# Power_Soldier.net
KiCad netlist of a schematic drawn in Altium Designer
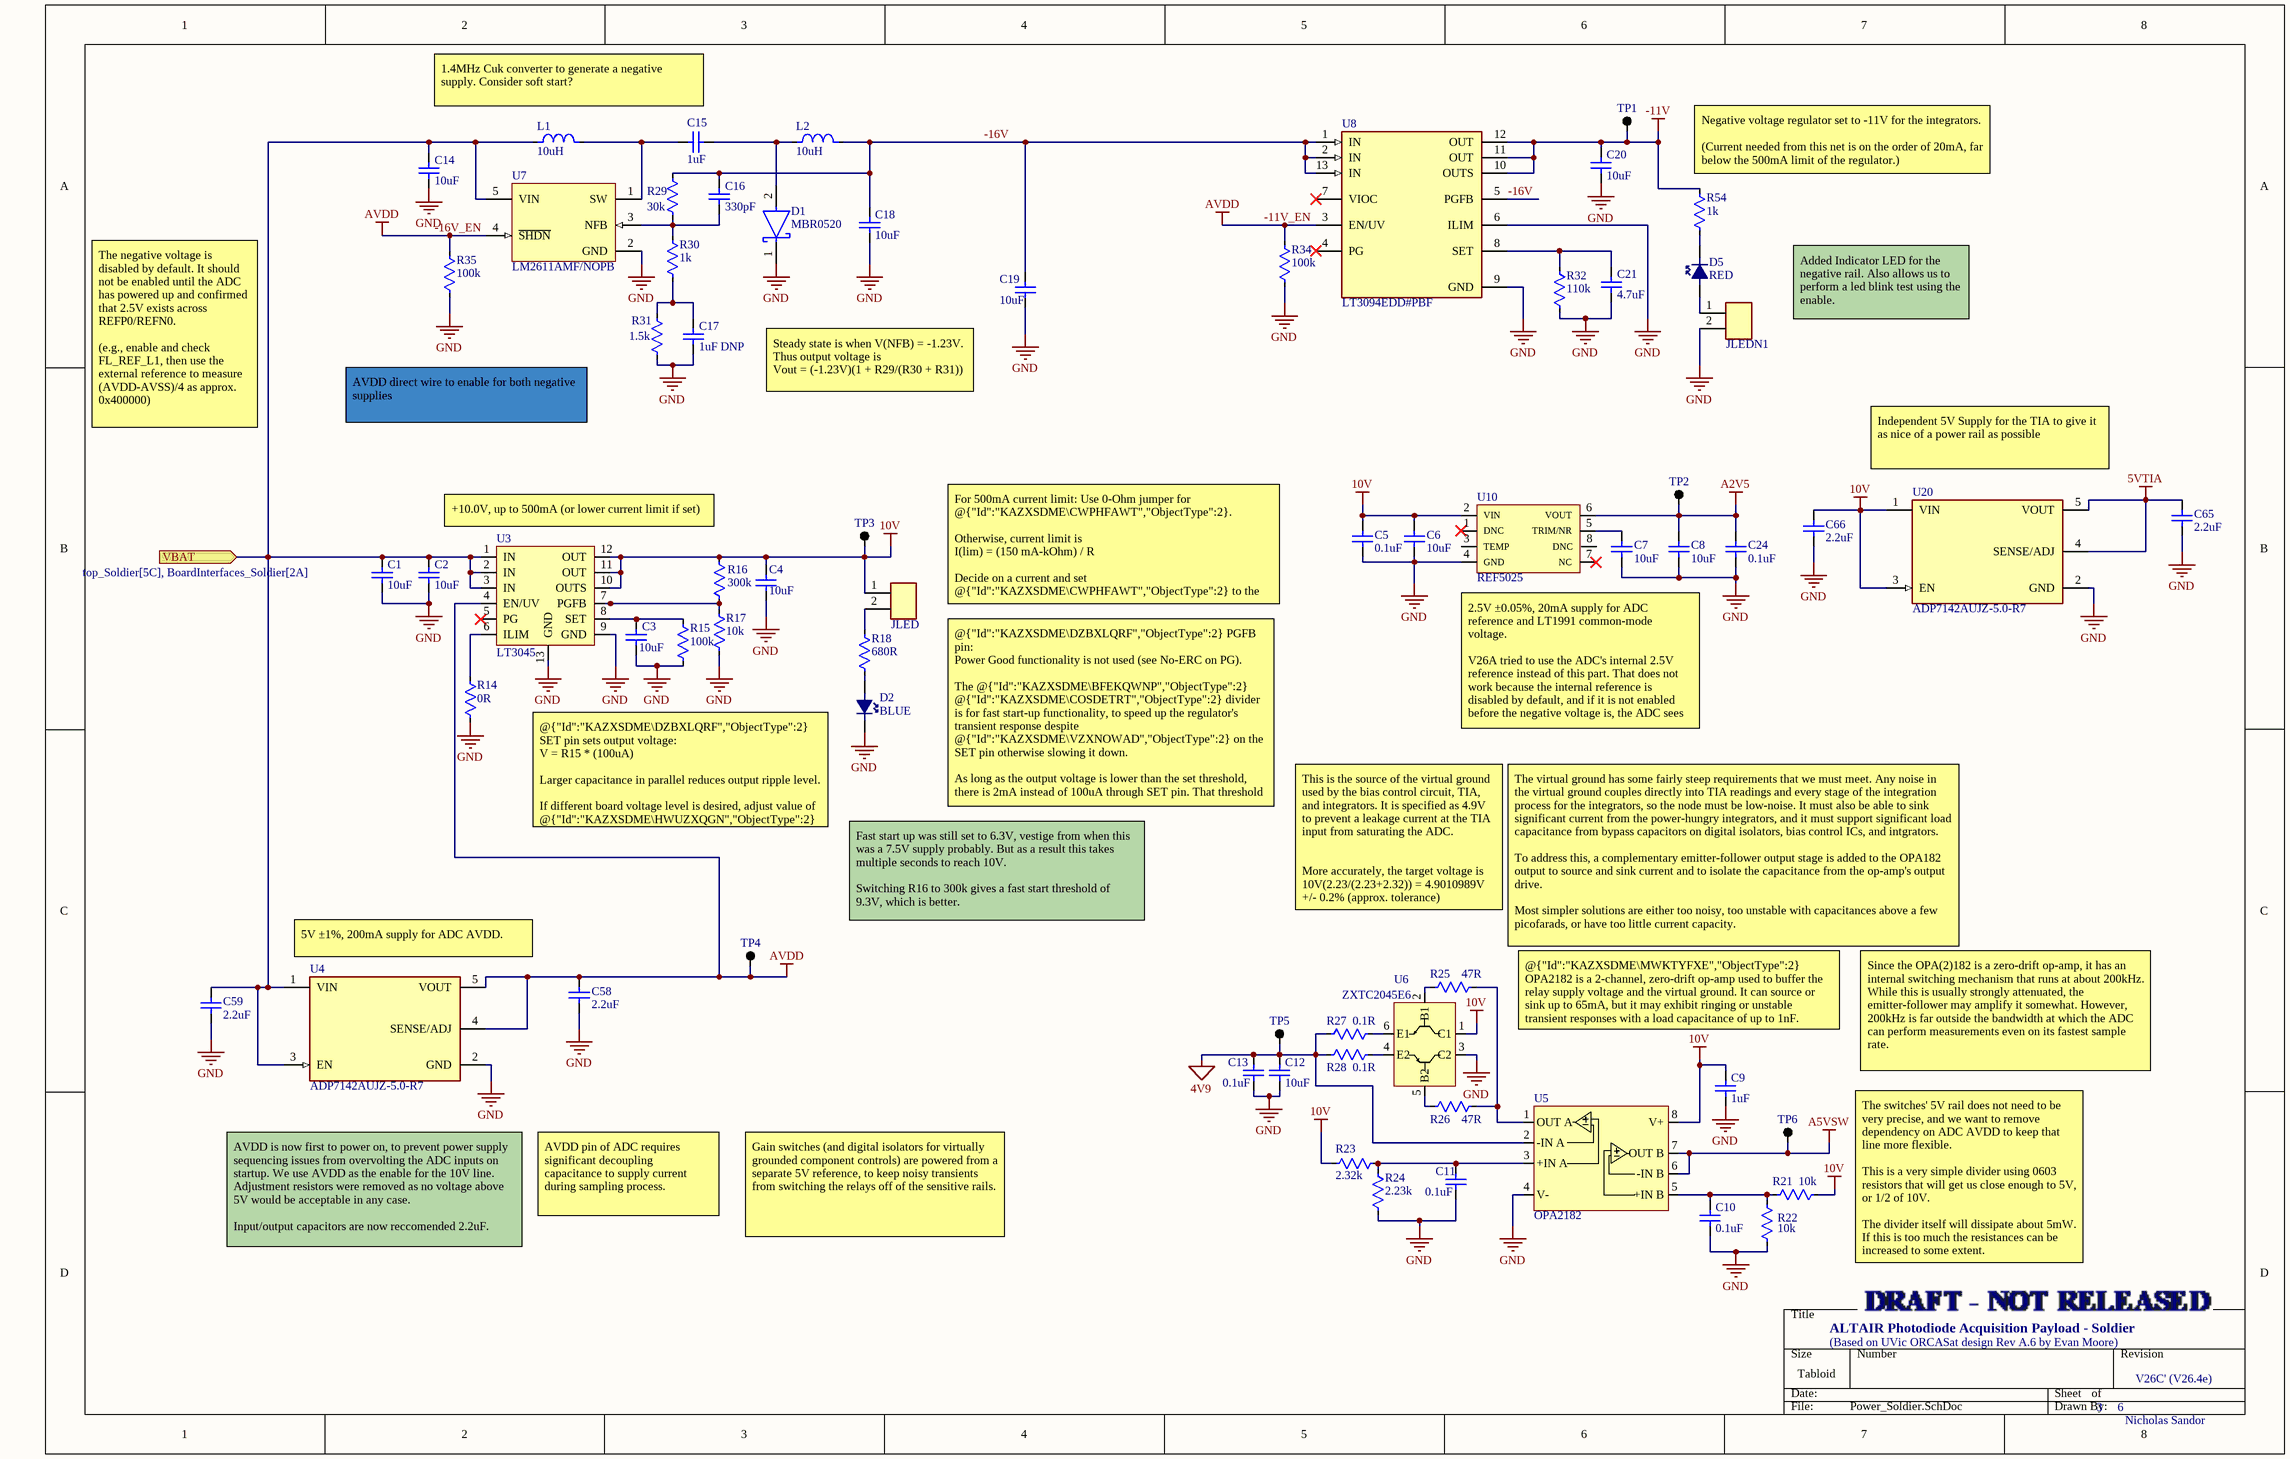
[diagram p0: Power_Soldier.SchDoc]

(export (version "E")
  (design (tool "Eeschema 10.0.6"))
  (components
    (comp (ref "C1")
      (value "10uF")
      (footprint "CAP 1206 IPC LOW DENSITY")
      (description "Murata GRT319R6YA106KE01D - Cap Ceramic 10uF 35V X5R 10% Pad SMD 1206 85C Automotive T/R")
      (fields (field (name "MF") "Murata") (field (name "MP") "GRT319R6YA106KE01D"))
      (libsource (lib "ALTAIR_PD_Capacitors") (part "CAP"))
    )
    (comp (ref "C2")
      (value "10uF")
      (footprint "CAP 1206 IPC LOW DENSITY")
      (description "Murata GRT319R6YA106KE01D - Cap Ceramic 10uF 35V X5R 10% Pad SMD 1206 85C Automotive T/R")
      (fields (field (name "MF") "Murata") (field (name "MP") "GRT319R6YA106KE01D"))
      (libsource (lib "ALTAIR_PD_Capacitors") (part "CAP"))
    )
    (comp (ref "C3")
      (value "10uF")
      (footprint "CAP 1206 IPC LOW DENSITY")
      (description "Murata GRT319R6YA106KE01D - Cap Ceramic 10uF 35V X5R 10% Pad SMD 1206 85C Automotive T/R")
      (fields (field (name "MF") "Murata") (field (name "MP") "GRT319R6YA106KE01D"))
      (libsource (lib "ALTAIR_PD_Capacitors") (part "CAP"))
    )
    (comp (ref "C4")
      (value "10uF")
      (footprint "CAP 1206 IPC LOW DENSITY")
      (description "Murata GRT319R6YA106KE01D - Cap Ceramic 10uF 35V X5R 10% Pad SMD 1206 85C Automotive T/R")
      (fields (field (name "MF") "Murata") (field (name "MP") "GRT319R6YA106KE01D"))
      (libsource (lib "ALTAIR_PD_Capacitors") (part "CAP"))
    )
    (comp (ref "C5")
      (value "0.1uF")
      (footprint "CAP 0603 IPC MID DENSITY")
      (description "Kemet C0603C104K5RACAUTO - Cap Ceramic 0.1uF 50V X7R 10% 0603 125C Paper T/R")
      (fields (field (name "MF") "Kemet") (field (name "MP") "C0603C104K5RACAUTO"))
      (libsource (lib "ALTAIR_PD_Capacitors") (part "CAP"))
    )
    (comp (ref "C6")
      (value "10uF")
      (footprint "CAP 0805 IPC MID DENSITY")
      (description "Murata GRM21BR61E106KA73L - Cap Ceramic 10uF 10% 25V X5R 0805")
      (fields (field (name "MF") "Murata") (field (name "MP") "GRM21BR61E106KA73L"))
      (libsource (lib "ALTAIR_PD_Capacitors") (part "CAP"))
    )
    (comp (ref "C7")
      (value "10uF")
      (footprint "CAP 0805 IPC MID DENSITY")
      (description "Murata GRM21BR61E106KA73L - Cap Ceramic 10uF 10% 25V X5R 0805")
      (fields (field (name "MF") "Murata") (field (name "MP") "GRM21BR61E106KA73L"))
      (libsource (lib "ALTAIR_PD_Capacitors") (part "CAP"))
    )
    (comp (ref "C8")
      (value "10uF")
      (footprint "CAP 0805 IPC MID DENSITY")
      (description "Murata GRM21BR61E106KA73L - Cap Ceramic 10uF 10% 25V X5R 0805")
      (fields (field (name "MF") "Murata") (field (name "MP") "GRM21BR61E106KA73L"))
      (libsource (lib "ALTAIR_PD_Capacitors") (part "CAP"))
    )
    (comp (ref "C9")
      (value "1uF")
      (footprint "CAP 0603 IPC MID DENSITY")
      (description "Murata GRT188R61H105KE13D - Cap MLCC AEC-Q200 X5R 1uF 50V 0603")
      (fields (field (name "MF") "Murata") (field (name "MP") "GRT188R61H105KE13D"))
      (libsource (lib "ALTAIR_PD_Capacitors") (part "CAP"))
    )
    (comp (ref "C10")
      (value "0.1uF")
      (footprint "CAP 0603 IPC MID DENSITY")
      (description "Kemet C0603C104K5RACAUTO - Cap Ceramic 0.1uF 50V X7R 10% 0603 125C Paper T/R")
      (fields (field (name "MF") "Kemet") (field (name "MP") "C0603C104K5RACAUTO"))
      (libsource (lib "ALTAIR_PD_Capacitors") (part "CAP"))
    )
    (comp (ref "C11")
      (value "0.1uF")
      (footprint "CAP 0603 IPC MID DENSITY")
      (description "Kemet C0603C104K5RACAUTO - Cap Ceramic 0.1uF 50V X7R 10% 0603 125C Paper T/R")
      (fields (field (name "MF") "Kemet") (field (name "MP") "C0603C104K5RACAUTO"))
      (libsource (lib "ALTAIR_PD_Capacitors") (part "CAP"))
    )
    (comp (ref "C12")
      (value "10uF")
      (footprint "CAP 1206 IPC LOW DENSITY")
      (description "Murata GRT319R6YA106KE01D - Cap Ceramic 10uF 35V X5R 10% Pad SMD 1206 85C Automotive T/R")
      (fields (field (name "MF") "Murata") (field (name "MP") "GRT319R6YA106KE01D"))
      (libsource (lib "ALTAIR_PD_Capacitors") (part "CAP"))
    )
    (comp (ref "C13")
      (value "0.1uF")
      (footprint "CAP 0603 IPC MID DENSITY")
      (description "Kemet C0603C104K5RACAUTO - Cap Ceramic 0.1uF 50V X7R 10% 0603 125C Paper T/R")
      (fields (field (name "MF") "Kemet") (field (name "MP") "C0603C104K5RACAUTO"))
      (libsource (lib "ALTAIR_PD_Capacitors") (part "CAP"))
    )
    (comp (ref "C14")
      (value "10uF")
      (footprint "CAP 0805 IPC MID DENSITY")
      (description "Murata GRM21BR61E106KA73L - Cap Ceramic 10uF 10% 25V X5R 0805")
      (fields (field (name "MF") "Murata") (field (name "MP") "GRM21BR61E106KA73L"))
      (libsource (lib "ALTAIR_PD_Capacitors") (part "CAP"))
    )
    (comp (ref "C15")
      (value "1uF")
      (footprint "CAP 0603 IPC MID DENSITY")
      (description "Murata GRT188R61H105KE13D - Cap MLCC AEC-Q200 X5R 1uF 50V 0603")
      (fields (field (name "MF") "Murata") (field (name "MP") "GRT188R61H105KE13D"))
      (libsource (lib "ALTAIR_PD_Capacitors") (part "CAP"))
    )
    (comp (ref "C16")
      (value "330pF")
      (footprint "CAP 1206 NON-IPC KEMET NP0")
      (description "Kemet C1206C331J5GACTU - Cap Ceramic 330pF 50V 5% NP0 1206")
      (fields (field (name "MF") "Kemet") (field (name "MP") "C1206C331J5GACTU"))
      (libsource (lib "ALTAIR_PD_Capacitors") (part "CAP"))
    )
    (comp (ref "C17")
      (value "1uF DNP")
      (footprint "CAP 0603 IPC MID DENSITY")
      (description "Murata GRT188R61H105KE13D - Cap MLCC AEC-Q200 X5R 1uF 50V 0603")
      (fields (field (name "MF") "Murata") (field (name "MP") "GRT188R61H105KE13D"))
      (libsource (lib "ALTAIR_PD_Capacitors") (part "CAP"))
    )
    (comp (ref "C18")
      (value "10uF")
      (footprint "CAP 0805 IPC MID DENSITY")
      (description "Murata GRM21BR61E106KA73L - Cap Ceramic 10uF 10% 25V X5R 0805")
      (fields (field (name "MF") "Murata") (field (name "MP") "GRM21BR61E106KA73L"))
      (libsource (lib "ALTAIR_PD_Capacitors") (part "CAP"))
    )
    (comp (ref "C19")
      (value "10uF")
      (footprint "CAP 0805 IPC MID DENSITY")
      (description "Murata GRM21BR61E106KA73L - Cap Ceramic 10uF 10% 25V X5R 0805")
      (fields (field (name "MF") "Murata") (field (name "MP") "GRM21BR61E106KA73L"))
      (libsource (lib "ALTAIR_PD_Capacitors") (part "CAP"))
    )
    (comp (ref "C20")
      (value "10uF")
      (footprint "CAP 0805 IPC MID DENSITY")
      (description "Murata GRM21BR61E106KA73L - Cap Ceramic 10uF 10% 25V X5R 0805")
      (fields (field (name "MF") "Murata") (field (name "MP") "GRM21BR61E106KA73L"))
      (libsource (lib "ALTAIR_PD_Capacitors") (part "CAP"))
    )
    (comp (ref "C21")
      (value "4.7uF")
      (footprint "CAP 0805 NON-IPC KEMET X5R")
      (description "Kemet C0805C475K8PACTU - Cap Ceramic 4.7uF 10V X5R 0805")
      (fields (field (name "MF") "Kemet") (field (name "MP") "C0805C475K8PACTU"))
      (libsource (lib "ALTAIR_PD_Capacitors") (part "CAP"))
    )
    (comp (ref "C24")
      (value "0.1uF")
      (footprint "CAP 0603 IPC MID DENSITY")
      (description "Kemet C0603C104K5RACAUTO - Cap Ceramic 0.1uF 50V X7R 10% 0603 125C Paper T/R")
      (fields (field (name "MF") "Kemet") (field (name "MP") "C0603C104K5RACAUTO"))
      (libsource (lib "ALTAIR_PD_Capacitors") (part "CAP"))
    )
    (comp (ref "C58")
      (value "2.2uF")
      (footprint "CAP 1206 UNKNOWN")
      (description "CL31B225KBHNNNE CAP CER 2.2UF 50V X7R 1206")
      (fields (field (name "MF") "Samsung Electro-Mechanics") (field (name "MP") "CL31B225KBHNNNE"))
      (libsource (lib "ALTAIR_PD_Capacitors") (part "CAP"))
    )
    (comp (ref "C59")
      (value "2.2uF")
      (footprint "CAP 1206 UNKNOWN")
      (description "CL31B225KBHNNNE CAP CER 2.2UF 50V X7R 1206")
      (fields (field (name "MF") "Samsung Electro-Mechanics") (field (name "MP") "CL31B225KBHNNNE"))
      (libsource (lib "ALTAIR_PD_Capacitors") (part "CAP"))
    )
    (comp (ref "C65")
      (value "2.2uF")
      (footprint "CAP 1206 UNKNOWN")
      (description "CL31B225KBHNNNE CAP CER 2.2UF 50V X7R 1206")
      (fields (field (name "MF") "Samsung Electro-Mechanics") (field (name "MP") "CL31B225KBHNNNE"))
      (libsource (lib "ALTAIR_PD_Capacitors") (part "CAP"))
    )
    (comp (ref "C66")
      (value "2.2uF")
      (footprint "CAP 1206 UNKNOWN")
      (description "CL31B225KBHNNNE CAP CER 2.2UF 50V X7R 1206")
      (fields (field (name "MF") "Samsung Electro-Mechanics") (field (name "MP") "CL31B225KBHNNNE"))
      (libsource (lib "ALTAIR_PD_Capacitors") (part "CAP"))
    )
    (comp (ref "D1")
      (value "MBR0520")
      (footprint "SOD-123 ONSEMI SMALL PADS")
      (description "DIODE SCHOTTKY 20V 500MA SOD123")
      (fields (field (name "MF") "onsemi") (field (name "MP") "MBR0520LT1G"))
      (libsource (lib "ALTAIR_PD_Diodes") (part "Schottky"))
    )
    (comp (ref "D2")
      (value "BLUE")
      (footprint "LED 0603 MID DENSITY")
      (description "LED BLUE CLEAR 0603 SMD")
      (fields (field (name "MF") "Wurth Electronics") (field (name "MP") "150060BS75000"))
      (libsource (lib "ALTAIR_PD_Diodes") (part "LED-blue"))
    )
    (comp (ref "D5")
      (value "RED")
      (footprint "LED 0603 MID DENSITY")
      (description "LED RED CLEAR 0603 SMD")
      (fields (field (name "MF") "Wurth Electronics") (field (name "MP") "150060BS75000"))
      (libsource (lib "ALTAIR_PD_Diodes") (part "LED-blue"))
    )
    (comp (ref "JLED")
      (value "JLED")
      (footprint "ALTAIR_PD_Headers:JUMPER 2POS 1MM PITCH THT")
      (description "2x1 Header THT 1mm Pitch")
      (fields
        (field (name "MF") "GCT (GLOBAL CONNECTOR TECHNOLOGY)")
        (field (name "MP") "BC020-02-A-0200-0300-L-G")
      )
      (libsource (lib "ALTAIR_PD_Headers") (part "BC020-02-A-0200-0300-L-G"))
    )
    (comp (ref "JLEDN1")
      (value "JLED")
      (footprint "ALTAIR_PD_Headers:JUMPER 2POS 1MM PITCH THT")
      (description "2x1 Header THT 1mm Pitch")
      (fields
        (field (name "MF") "GCT (GLOBAL CONNECTOR TECHNOLOGY)")
        (field (name "MP") "BC020-02-A-0200-0300-L-G")
      )
      (libsource (lib "ALTAIR_PD_Headers") (part "BC020-02-A-0200-0300-L-G"))
    )
    (comp (ref "L1")
      (value "10uH")
      (footprint "IND VLS3012CX-1 NONSTANDARD TDK")
      (description "TDK VLS3012CX-100M-1 - Inductor 10uH 20% 1.25A 0.324Ohm NonstandardPkg")
      (fields (field (name "TOLERANCE") "20%") (field (name "MF") "TDK Corporation"))
      (libsource (lib "ALTAIR_PD_Inductors") (part "IND"))
    )
    (comp (ref "L2")
      (value "10uH")
      (footprint "IND VLS3012CX-1 NONSTANDARD TDK")
      (description "TDK VLS3012CX-100M-1 - Inductor 10uH 20% 1.25A 0.324Ohm NonstandardPkg")
      (fields (field (name "TOLERANCE") "20%") (field (name "MF") "TDK Corporation"))
      (libsource (lib "ALTAIR_PD_Inductors") (part "IND"))
    )
    (comp (ref "R14")
      (value "0R")
      (footprint "RES 0603 IPC MID DENSITY")
      (description "Vishay CRCW06030000Z0EA - Res 0 Ohms 1/8W SMD 0603")
      (fields (field (name "MF") "Vishay Dale") (field (name "MP") "CRCW06030000Z0EA"))
      (libsource (lib "ALTAIR_PD_Resistors") (part "RES"))
    )
    (comp (ref "R15")
      (value "100k")
      (footprint "RES 0603 IPC MID DENSITY")
      (description "Panasonic ERA-3ARB104V - Res SMD 0603 0.1% 0.10W T.C. 10ppm 100K")
      (fields (field (name "MF") "Panasonic Electronic Components") (field (name "MP") "ERA-3ARB104V"))
      (libsource (lib "ALTAIR_PD_Resistors") (part "RES"))
    )
    (comp (ref "R16")
      (value "300k")
      (footprint "RES 0603 IPC MID DENSITY")
      (description "Vishay MCT06030C3003FP500 - Res SMD 300kOhm 1% 1/10W 0603")
      (fields (field (name "MF") "Vishay Dale") (field (name "MP") "MCT06030C3003FP500"))
      (libsource (lib "ALTAIR_PD_Resistors") (part "RES"))
    )
    (comp (ref "R17")
      (value "10k")
      (footprint "RES 0603 IPC MID DENSITY")
      (description "Vishay CRCW060310K0FKEA SMD 0603 10k, CRCW e3 Series, 75V, thick film, 100mW")
      (fields (field (name "MF") "Vishay Dale") (field (name "MP") "CRCW060310K0FKEA"))
      (libsource (lib "ALTAIR_PD_Resistors") (part "RES"))
    )
    (comp (ref "R18")
      (value "680R")
      (footprint "RES 0603 IPC MID DENSITY")
      (description "Panasonic ERJ-3EKF6800V - Res SMD 680 Ohm 1% 1/10W 0603")
      (fields (field (name "MF") "Panasonic Electronic Components") (field (name "MP") "ERJ-3EKF6800V"))
      (libsource (lib "ALTAIR_PD_Resistors") (part "RES"))
    )
    (comp (ref "R21")
      (value "10k")
      (footprint "RES 0603 IPC MID DENSITY")
      (description "Vishay CRCW060310K0FKEA SMD 0603 10k, CRCW e3 Series, 75V, thick film, 100mW")
      (fields (field (name "MF") "Vishay Dale") (field (name "MP") "CRCW060310K0FKEA"))
      (libsource (lib "ALTAIR_PD_Resistors") (part "RES"))
    )
    (comp (ref "R22")
      (value "10k")
      (footprint "RES 0603 IPC MID DENSITY")
      (description "Vishay CRCW060310K0FKEA SMD 0603 10k, CRCW e3 Series, 75V, thick film, 100mW")
      (fields (field (name "MF") "Vishay Dale") (field (name "MP") "CRCW060310K0FKEA"))
      (libsource (lib "ALTAIR_PD_Resistors") (part "RES"))
    )
    (comp (ref "R23")
      (value "2.32k")
      (footprint "RES 0603 IPC MID DENSITY")
      (description "Vishay TNPW06032K32BEEA - Res 2.32k 0.1% 0.21W SMD 0603")
      (fields (field (name "MF") "Vishay Dale") (field (name "MP") "TNPW06032K32BEEA"))
      (libsource (lib "ALTAIR_PD_Resistors") (part "RES"))
    )
    (comp (ref "R24")
      (value "2.23k")
      (footprint "RES 0603 IPC MID DENSITY")
      (description "KOA Speer RN73R1JTTD2231B25 - Res 2.23k 0.1% 1/10W SMD 0603")
      (fields (field (name "MF") "KOA Speer Electronics, Inc.") (field (name "MP") "RN73R1JTTD2231B25"))
      (libsource (lib "ALTAIR_PD_Resistors") (part "RES"))
    )
    (comp (ref "R25")
      (value "47R")
      (footprint "RES 0402 NON-IPC SEI")
      (description "Stackpole RMCF0402JT47R0 - Res 47Ohm 5% 0.063W 0402 Thick Film AEC-Q200 compliant")
      (fields (field (name "MF") "Stackpole Electronics Inc.") (field (name "MP") "RMCF0402JT47R0"))
      (libsource (lib "ALTAIR_PD_Resistors") (part "RES"))
    )
    (comp (ref "R26")
      (value "47R")
      (footprint "RES 0402 NON-IPC SEI")
      (description "Stackpole RMCF0402JT47R0 - Res 47Ohm 5% 0.063W 0402 Thick Film AEC-Q200 compliant")
      (fields (field (name "MF") "Stackpole Electronics Inc.") (field (name "MP") "RMCF0402JT47R0"))
      (libsource (lib "ALTAIR_PD_Resistors") (part "RES"))
    )
    (comp (ref "R27")
      (value "0.1R")
      (footprint "RES 0402 NON-IPC YAGEO")
      (description "Yageo RL0402JR-070R1L - Res 0.1Ohm 5% 1/16W SMD 0402")
      (fields (field (name "MF") "YAGEO") (field (name "MP") "RL0402JR-070R1L"))
      (libsource (lib "ALTAIR_PD_Resistors") (part "RES"))
    )
    (comp (ref "R28")
      (value "0.1R")
      (footprint "RES 0402 NON-IPC YAGEO")
      (description "Yageo RL0402JR-070R1L - Res 0.1Ohm 5% 1/16W SMD 0402")
      (fields (field (name "MF") "YAGEO") (field (name "MP") "RL0402JR-070R1L"))
      (libsource (lib "ALTAIR_PD_Resistors") (part "RES"))
    )
    (comp (ref "R29")
      (value "30k")
      (footprint "RES 0805 IPC HIGH DENSITY")
      (description "Panasonic ERA-6AEB303V - Res 30kOhm 0.1% 1/8W 0805")
      (fields (field (name "MF") "Panasonic Electronic Components") (field (name "MP") "ERA-6AEB303V"))
      (libsource (lib "ALTAIR_PD_Resistors") (part "RES"))
    )
    (comp (ref "R30")
      (value "1k")
      (footprint "RES 0402 IPC LOW DENSITY YAGEO")
      (description "Yageo RC0402FR-071KL - Res 1kOhm 1% 1/16W 0402")
      (fields (field (name "MF") "YAGEO") (field (name "MP") "RC0402FR-071KL"))
      (libsource (lib "ALTAIR_PD_Resistors") (part "RES"))
    )
    (comp (ref "R31")
      (value "1.5k")
      (footprint "RES 1206 NON-IPC VISHAY")
      (description "Vishay TNPU12061K50BZEN00 - Res 1.5kOhm 0.1% 1/4W 1206")
      (fields (field (name "MF") "Vishay Dale") (field (name "MP") "TNPU12061K50BZEN00"))
      (libsource (lib "ALTAIR_PD_Resistors") (part "RES"))
    )
    (comp (ref "R32")
      (value "110k")
      (footprint "RES 0603 IPC MID DENSITY")
      (description "Panasonic ERA-3AEB114V - Res 110k 0.1% 1/10W SMD 0603")
      (fields (field (name "MF") "Panasonic Electronic Components") (field (name "MP") "ERA-3AEB114V"))
      (libsource (lib "ALTAIR_PD_Resistors") (part "RES"))
    )
    (comp (ref "R34")
      (value "100k")
      (footprint "RES 0603 IPC MID DENSITY")
      (description "Panasonic ERJ-3GEYJ104V - Res 100k 5% 1/10W SMD 0603")
      (fields (field (name "MF") "Panasonic Electronic Components") (field (name "MP") "ERJ-3GEYJ104V"))
      (libsource (lib "ALTAIR_PD_Resistors") (part "RES"))
    )
    (comp (ref "R35")
      (value "100k")
      (footprint "RES 0603 IPC MID DENSITY")
      (description "Panasonic ERJ-3GEYJ104V - Res 100k 5% 1/10W SMD 0603")
      (fields (field (name "MF") "Panasonic Electronic Components") (field (name "MP") "ERJ-3GEYJ104V"))
      (libsource (lib "ALTAIR_PD_Resistors") (part "RES"))
    )
    (comp (ref "R54")
      (value "1k")
      (footprint "RES 0603 IPC MID DENSITY")
      (description "Panasonic ERJ-U03F1001V - Res SMD 1 kOhm 1% 1/10W 0603")
      (fields (field (name "MF") "Panasonic Electronic Components") (field (name "MP") "ERJ-U03F1001V"))
      (libsource (lib "ALTAIR_PD_Resistors") (part "RES"))
    )
    (comp (ref "TP1")
      (value "Testpoint")
      (footprint "TESTPOINT THT")
      (libsource (lib "ALTAIR_PD_Testpoint") (part "Testpoint"))
    )
    (comp (ref "TP2")
      (value "Testpoint")
      (footprint "TESTPOINT THT")
      (libsource (lib "ALTAIR_PD_Testpoint") (part "Testpoint"))
    )
    (comp (ref "TP3")
      (value "Testpoint")
      (footprint "TESTPOINT THT")
      (libsource (lib "ALTAIR_PD_Testpoint") (part "Testpoint"))
    )
    (comp (ref "TP4")
      (value "Testpoint")
      (footprint "TESTPOINT THT")
      (libsource (lib "ALTAIR_PD_Testpoint") (part "Testpoint"))
    )
    (comp (ref "TP5")
      (value "Testpoint")
      (footprint "TESTPOINT THT")
      (libsource (lib "ALTAIR_PD_Testpoint") (part "Testpoint"))
    )
    (comp (ref "TP6")
      (value "Testpoint")
      (footprint "TESTPOINT THT")
      (libsource (lib "ALTAIR_PD_Testpoint") (part "Testpoint"))
    )
    (comp (ref "U3")
      (value "LT3045")
      (footprint "12-TSOP 0.65MM PITCH 3MM WIDTH EP IPC MID DENSITY")
      (description "20V 500mA Ultralow Noise Ultrahigh PSRR Adjustable Linear Regulator 260V Dropout MSOP-12")
      (fields (field (name "MF") "Analog Devices / Linear Technology") (field (name "MP") "LT3045EMSE#PBF"))
      (libsource (lib "ALTAIR_PD_Regulators") (part "LT3045"))
    )
    (comp (ref "U4")
      (value "ADP7142AUJZ-5.0-R7")
      (footprint "SOT23-5 HIGH DENSITY AD")
      (description "1.2-40V 200mA Low Noise CMOS LDO Adjustable Linear Regulator TSOT23")
      (fields
        (field (name "OCTOPART") "https://octopart.com/adp7142aujz-r7-analog+devices-38928114")
        (field (name "MF") "Analog Devices")
      )
      (libsource (lib "ALTAIR_PD_Regulators") (part "ADP7142AUJZ-R7"))
    )
    (comp (ref "U5")
      (value "OPA2182")
      (footprint "8-TSSOP 0.65MM PITCH 4.4MM WIDTH IPC MID DENSITY")
      (fields (field (name "MF") "Texas Instruments") (field (name "MP") "OPA2182IDGKR"))
      (libsource (lib "ALTAIR_PD_Amplifiers") (part "OPA2182IDBV"))
    )
    (comp (ref "U6")
      (value "ZXTC2045E6")
      (footprint "SOT23-6 NON-IPC DIODES")
      (description "BJT Array, 1NPN 1PNP, VCE(sat) 375mV, hFE 300, Breakdown 30V, 6-SOT-23")
      (fields (field (name "MF") "Diodes Incorporated") (field (name "MP") "ZXTC2045E6TA"))
      (libsource (lib "ALTAIR_PD_BJTs") (part "ZXTC2045E6"))
    )
    (comp (ref "U7")
      (value "LM2611AMF/NOPB")
      (footprint "SOT23-5 MID DENSITY")
      (description "1.4MHz Cuk Converter, 5-pin SOT-23, Pb-Free")
      (fields (field (name "MF") "Texas Instruments"))
      (libsource (lib "ALTAIR_PD_Converters") (part "LM2611AMF"))
    )
    (comp (ref "U8")
      (value "LT3094EDD#PBF")
      (footprint "12DFN 3x3MM EP IPC MID DENSITY")
      (description "-20V 500mA Ultralow Noise Ultrahigh PSRR Adjustable Negative Linear Regulator 12DFN")
      (fields (field (name "MF") "Analog Devices"))
      (libsource (lib "ALTAIR_PD_Regulators") (part "LT3094EDD#PBF"))
    )
    (comp (ref "U10")
      (value "REF5025")
      (footprint "8-TSOP 0.65MM PITCH 3MM WIDTH IPC MID DENSITY")
      (description "2.5V±0.05% Voltage Reference 8VSSOP")
      (fields (field (name "MF") "Texas Instruments") (field (name "MP") "REF5025IDGKR"))
      (libsource (lib "ALTAIR_PD_MiscPower") (part "REF5050IDGKR"))
    )
    (comp (ref "U20")
      (value "ADP7142AUJZ-5.0-R7")
      (footprint "SOT23-5 HIGH DENSITY AD")
      (description "1.2-40V 200mA Low Noise CMOS LDO Adjustable Linear Regulator TSOT23")
      (fields
        (field (name "OCTOPART") "https://octopart.com/adp7142aujz-r7-analog+devices-38928114")
        (field (name "MF") "Analog Devices")
      )
      (libsource (lib "ALTAIR_PD_Regulators") (part "ADP7142AUJZ-R7"))
    )
  )
  (nets
    (net (code "1") (name "-11V") (class "Default")
      (node (ref "C20") (pin "1") (pinfunction "1_1") (pintype "passive"))
      (node (ref "R54") (pin "2") (pinfunction "2_2") (pintype "passive"))
      (node (ref "TP1") (pin "1") (pinfunction "1_1") (pintype "passive"))
      (node (ref "U8") (pin "10") (pinfunction "OUTS_10") (pintype "power_in"))
      (node (ref "U8") (pin "11") (pinfunction "OUT_11") (pintype "power_in"))
      (node (ref "U8") (pin "12") (pinfunction "OUT_12") (pintype "power_in"))
    )
    (net (code "2") (name "/-16V") (class "Default")
      (node (ref "C16") (pin "1") (pinfunction "1_1") (pintype "passive"))
      (node (ref "C18") (pin "1") (pinfunction "1_1") (pintype "passive"))
      (node (ref "C19") (pin "1") (pinfunction "1_1") (pintype "passive"))
      (node (ref "L2") (pin "2") (pinfunction "2_2") (pintype "passive"))
      (node (ref "R29") (pin "2") (pinfunction "2_2") (pintype "passive"))
      (node (ref "U8") (pin "1") (pinfunction "IN_1") (pintype "input"))
      (node (ref "U8") (pin "13") (pinfunction "IN_13") (pintype "input"))
      (node (ref "U8") (pin "2") (pinfunction "IN_2") (pintype "input"))
      (node (ref "U8") (pin "5") (pinfunction "PGFB_5") (pintype "passive"))
    )
    (net (code "3") (name "/VBAT") (class "Default")
      (node (ref "C1") (pin "2") (pinfunction "2_2") (pintype "passive"))
      (node (ref "C14") (pin "2") (pinfunction "2_2") (pintype "passive"))
      (node (ref "C2") (pin "2") (pinfunction "2_2") (pintype "passive"))
      (node (ref "C59") (pin "1") (pinfunction "1_1") (pintype "passive"))
      (node (ref "L1") (pin "1") (pinfunction "1_1") (pintype "passive"))
      (node (ref "U3") (pin "1") (pinfunction "IN_1") (pintype "passive"))
      (node (ref "U3") (pin "2") (pinfunction "IN_2") (pintype "passive"))
      (node (ref "U3") (pin "3") (pinfunction "IN_3") (pintype "passive"))
      (node (ref "U4") (pin "1") (pinfunction "VIN_1") (pintype "power_in"))
      (node (ref "U4") (pin "3") (pinfunction "EN_3") (pintype "input"))
      (node (ref "U7") (pin "5") (pinfunction "VIN_5") (pintype "power_in"))
    )
    (net (code "4") (name "4V9") (class "Default")
      (node (ref "C12") (pin "2") (pinfunction "2_2") (pintype "passive"))
      (node (ref "C13") (pin "2") (pinfunction "2_2") (pintype "passive"))
      (node (ref "R27") (pin "1") (pinfunction "1_1") (pintype "passive"))
      (node (ref "R28") (pin "1") (pinfunction "1_1") (pintype "passive"))
      (node (ref "TP5") (pin "1") (pinfunction "1_1") (pintype "passive"))
      (node (ref "U5") (pin "2") (pinfunction "-IN_A_2") (pintype "passive"))
    )
    (net (code "5") (name "5VTIA") (class "Default")
      (node (ref "C65") (pin "1") (pinfunction "1_1") (pintype "passive"))
      (node (ref "U20") (pin "4") (pinfunction "SENSE/ADJ_4") (pintype "passive"))
      (node (ref "U20") (pin "5") (pinfunction "VOUT_5") (pintype "passive"))
    )
    (net (code "6") (name "10V") (class "Default")
      (node (ref "C4") (pin "2") (pinfunction "2_2") (pintype "passive"))
      (node (ref "C5") (pin "1") (pinfunction "1_1") (pintype "passive"))
      (node (ref "C6") (pin "2") (pinfunction "2_2") (pintype "passive"))
      (node (ref "C66") (pin "1") (pinfunction "1_1") (pintype "passive"))
      (node (ref "C9") (pin "2") (pinfunction "2_2") (pintype "passive"))
      (node (ref "JLED") (pin "1") (pinfunction "1_1") (pintype "passive"))
      (node (ref "R16") (pin "2") (pinfunction "2_2") (pintype "passive"))
      (node (ref "R21") (pin "2") (pinfunction "2_2") (pintype "passive"))
      (node (ref "R23") (pin "2") (pinfunction "2_2") (pintype "passive"))
      (node (ref "TP3") (pin "1") (pinfunction "1_1") (pintype "passive"))
      (node (ref "U10") (pin "2") (pinfunction "VIN_2") (pintype "passive"))
      (node (ref "U20") (pin "1") (pinfunction "VIN_1") (pintype "power_in"))
      (node (ref "U20") (pin "3") (pinfunction "EN_3") (pintype "input"))
      (node (ref "U3") (pin "10") (pinfunction "OUTS_10") (pintype "passive"))
      (node (ref "U3") (pin "11") (pinfunction "OUT_11") (pintype "passive"))
      (node (ref "U3") (pin "12") (pinfunction "OUT_12") (pintype "passive"))
      (node (ref "U5") (pin "8") (pinfunction "V+_8") (pintype "passive"))
      (node (ref "U6") (pin "1") (pinfunction "C1_1") (pintype "passive"))
    )
    (net (code "7") (name "A2V5") (class "Default")
      (node (ref "C24") (pin "1") (pinfunction "1_1") (pintype "passive"))
      (node (ref "C8") (pin "2") (pinfunction "2_2") (pintype "passive"))
      (node (ref "TP2") (pin "1") (pinfunction "1_1") (pintype "passive"))
      (node (ref "U10") (pin "6") (pinfunction "VOUT_6") (pintype "passive"))
    )
    (net (code "8") (name "A5VSW") (class "Default")
      (node (ref "TP6") (pin "1") (pinfunction "1_1") (pintype "passive"))
      (node (ref "U5") (pin "6") (pinfunction "-IN_B_6") (pintype "passive"))
      (node (ref "U5") (pin "7") (pinfunction "OUT_B_7") (pintype "passive"))
    )
    (net (code "9") (name "AVDD") (class "Default")
      (node (ref "C58") (pin "1") (pinfunction "1_1") (pintype "passive"))
      (node (ref "R34") (pin "1") (pinfunction "1_1") (pintype "passive"))
      (node (ref "R35") (pin "1") (pinfunction "1_1") (pintype "passive"))
      (node (ref "TP4") (pin "1") (pinfunction "1_1") (pintype "passive"))
      (node (ref "U3") (pin "4") (pinfunction "EN/UV_4") (pintype "passive"))
      (node (ref "U4") (pin "4") (pinfunction "SENSE/ADJ_4") (pintype "passive"))
      (node (ref "U4") (pin "5") (pinfunction "VOUT_5") (pintype "passive"))
      (node (ref "U7") (pin "4") (pinfunction "~{SHDN}_4") (pintype "input"))
      (node (ref "U8") (pin "3") (pinfunction "EN/UV_3") (pintype "passive"))
    )
    (net (code "10") (name "GND") (class "Default")
      (node (ref "C1") (pin "1") (pinfunction "1_1") (pintype "passive"))
      (node (ref "C10") (pin "1") (pinfunction "1_1") (pintype "passive"))
      (node (ref "C11") (pin "1") (pinfunction "1_1") (pintype "passive"))
      (node (ref "C12") (pin "1") (pinfunction "1_1") (pintype "passive"))
      (node (ref "C13") (pin "1") (pinfunction "1_1") (pintype "passive"))
      (node (ref "C14") (pin "1") (pinfunction "1_1") (pintype "passive"))
      (node (ref "C17") (pin "2") (pinfunction "2_2") (pintype "passive"))
      (node (ref "C18") (pin "2") (pinfunction "2_2") (pintype "passive"))
      (node (ref "C19") (pin "2") (pinfunction "2_2") (pintype "passive"))
      (node (ref "C2") (pin "1") (pinfunction "1_1") (pintype "passive"))
      (node (ref "C20") (pin "2") (pinfunction "2_2") (pintype "passive"))
      (node (ref "C21") (pin "2") (pinfunction "2_2") (pintype "passive"))
      (node (ref "C24") (pin "2") (pinfunction "2_2") (pintype "passive"))
      (node (ref "C3") (pin "1") (pinfunction "1_1") (pintype "passive"))
      (node (ref "C4") (pin "1") (pinfunction "1_1") (pintype "passive"))
      (node (ref "C5") (pin "2") (pinfunction "2_2") (pintype "passive"))
      (node (ref "C58") (pin "2") (pinfunction "2_2") (pintype "passive"))
      (node (ref "C59") (pin "2") (pinfunction "2_2") (pintype "passive"))
      (node (ref "C6") (pin "1") (pinfunction "1_1") (pintype "passive"))
      (node (ref "C65") (pin "2") (pinfunction "2_2") (pintype "passive"))
      (node (ref "C66") (pin "2") (pinfunction "2_2") (pintype "passive"))
      (node (ref "C7") (pin "2") (pinfunction "2_2") (pintype "passive"))
      (node (ref "C8") (pin "1") (pinfunction "1_1") (pintype "passive"))
      (node (ref "C9") (pin "1") (pinfunction "1_1") (pintype "passive"))
      (node (ref "D1") (pin "1") (pinfunction "C_1") (pintype "passive"))
      (node (ref "D2") (pin "1") (pinfunction "1_1") (pintype "passive"))
      (node (ref "JLEDN1") (pin "2") (pinfunction "2_2") (pintype "passive"))
      (node (ref "R14") (pin "1") (pinfunction "1_1") (pintype "passive"))
      (node (ref "R15") (pin "1") (pinfunction "1_1") (pintype "passive"))
      (node (ref "R17") (pin "1") (pinfunction "1_1") (pintype "passive"))
      (node (ref "R22") (pin "1") (pinfunction "1_1") (pintype "passive"))
      (node (ref "R24") (pin "1") (pinfunction "1_1") (pintype "passive"))
      (node (ref "R31") (pin "1") (pinfunction "1_1") (pintype "passive"))
      (node (ref "R32") (pin "2") (pinfunction "2_2") (pintype "passive"))
      (node (ref "R34") (pin "2") (pinfunction "2_2") (pintype "passive"))
      (node (ref "R35") (pin "2") (pinfunction "2_2") (pintype "passive"))
      (node (ref "U10") (pin "4") (pinfunction "GND_4") (pintype "passive"))
      (node (ref "U20") (pin "2") (pinfunction "GND_2") (pintype "power_in"))
      (node (ref "U3") (pin "13") (pinfunction "GND_13") (pintype "passive"))
      (node (ref "U3") (pin "9") (pinfunction "GND_9") (pintype "passive"))
      (node (ref "U4") (pin "2") (pinfunction "GND_2") (pintype "power_in"))
      (node (ref "U5") (pin "4") (pinfunction "V-_4") (pintype "passive"))
      (node (ref "U6") (pin "3") (pinfunction "C2_3") (pintype "passive"))
      (node (ref "U7") (pin "2") (pinfunction "GND_2") (pintype "power_in"))
      (node (ref "U8") (pin "6") (pinfunction "ILIM_6") (pintype "passive"))
      (node (ref "U8") (pin "9") (pinfunction "GND_9") (pintype "power_in"))
    )
    (net (code "11") (name "Net-(C17-Pad1)") (class "Default")
      (node (ref "C17") (pin "1") (pinfunction "1_1") (pintype "passive"))
      (node (ref "R30") (pin "1") (pinfunction "1_1") (pintype "passive"))
      (node (ref "R31") (pin "2") (pinfunction "2_2") (pintype "passive"))
    )
    (net (code "12") (name "Net-(D1-A)") (class "Default")
      (node (ref "C15") (pin "2") (pinfunction "2_2") (pintype "passive"))
      (node (ref "D1") (pin "2") (pinfunction "A_2") (pintype "passive"))
      (node (ref "L2") (pin "1") (pinfunction "1_1") (pintype "passive"))
    )
    (net (code "13") (name "Net-(D2-Pad2)") (class "Default")
      (node (ref "D2") (pin "2") (pinfunction "2_2") (pintype "passive"))
      (node (ref "R18") (pin "1") (pinfunction "1_1") (pintype "passive"))
    )
    (net (code "14") (name "Net-(D5-Pad1)") (class "Default")
      (node (ref "D5") (pin "1") (pinfunction "1_1") (pintype "passive"))
      (node (ref "R54") (pin "1") (pinfunction "1_1") (pintype "passive"))
    )
    (net (code "15") (name "Net-(D5-Pad2)") (class "Default")
      (node (ref "D5") (pin "2") (pinfunction "2_2") (pintype "passive"))
      (node (ref "JLEDN1") (pin "1") (pinfunction "1_1") (pintype "passive"))
    )
    (net (code "16") (name "Net-(JLED-Pad2)") (class "Default")
      (node (ref "JLED") (pin "2") (pinfunction "2_2") (pintype "passive"))
      (node (ref "R18") (pin "2") (pinfunction "2_2") (pintype "passive"))
    )
    (net (code "17") (name "Net-(U3-ILIM)") (class "Default")
      (node (ref "R14") (pin "2") (pinfunction "2_2") (pintype "passive"))
      (node (ref "U3") (pin "6") (pinfunction "ILIM_6") (pintype "passive"))
    )
    (net (code "18") (name "Net-(U3-PGFB)") (class "Default")
      (node (ref "R16") (pin "1") (pinfunction "1_1") (pintype "passive"))
      (node (ref "R17") (pin "2") (pinfunction "2_2") (pintype "passive"))
      (node (ref "U3") (pin "7") (pinfunction "PGFB_7") (pintype "passive"))
    )
    (net (code "19") (name "Net-(U3-SET)") (class "Default")
      (node (ref "C3") (pin "2") (pinfunction "2_2") (pintype "passive"))
      (node (ref "R15") (pin "2") (pinfunction "2_2") (pintype "passive"))
      (node (ref "U3") (pin "8") (pinfunction "SET_8") (pintype "passive"))
    )
    (net (code "20") (name "Net-(U5-+IN_A)") (class "Default")
      (node (ref "C11") (pin "2") (pinfunction "2_2") (pintype "passive"))
      (node (ref "R23") (pin "1") (pinfunction "1_1") (pintype "passive"))
      (node (ref "R24") (pin "2") (pinfunction "2_2") (pintype "passive"))
      (node (ref "U5") (pin "3") (pinfunction "+IN_A_3") (pintype "passive"))
    )
    (net (code "21") (name "Net-(U5-+IN_B)") (class "Default")
      (node (ref "C10") (pin "2") (pinfunction "2_2") (pintype "passive"))
      (node (ref "R21") (pin "1") (pinfunction "1_1") (pintype "passive"))
      (node (ref "R22") (pin "2") (pinfunction "2_2") (pintype "passive"))
      (node (ref "U5") (pin "5") (pinfunction "+IN_B_5") (pintype "passive"))
    )
    (net (code "22") (name "Net-(U5-OUT_A)") (class "Default")
      (node (ref "R25") (pin "2") (pinfunction "2_2") (pintype "passive"))
      (node (ref "R26") (pin "2") (pinfunction "2_2") (pintype "passive"))
      (node (ref "U5") (pin "1") (pinfunction "OUT_A_1") (pintype "passive"))
    )
    (net (code "23") (name "Net-(U6-B1)") (class "Default")
      (node (ref "R25") (pin "1") (pinfunction "1_1") (pintype "passive"))
      (node (ref "U6") (pin "2") (pinfunction "B1_2") (pintype "passive"))
    )
    (net (code "24") (name "Net-(U6-B2)") (class "Default")
      (node (ref "R26") (pin "1") (pinfunction "1_1") (pintype "passive"))
      (node (ref "U6") (pin "5") (pinfunction "B2_5") (pintype "passive"))
    )
    (net (code "25") (name "Net-(U6-E1)") (class "Default")
      (node (ref "R27") (pin "2") (pinfunction "2_2") (pintype "passive"))
      (node (ref "U6") (pin "6") (pinfunction "E1_6") (pintype "passive"))
    )
    (net (code "26") (name "Net-(U6-E2)") (class "Default")
      (node (ref "R28") (pin "2") (pinfunction "2_2") (pintype "passive"))
      (node (ref "U6") (pin "4") (pinfunction "E2_4") (pintype "passive"))
    )
    (net (code "27") (name "Net-(U7-NFB)") (class "Default")
      (node (ref "C16") (pin "2") (pinfunction "2_2") (pintype "passive"))
      (node (ref "R29") (pin "1") (pinfunction "1_1") (pintype "passive"))
      (node (ref "R30") (pin "2") (pinfunction "2_2") (pintype "passive"))
      (node (ref "U7") (pin "3") (pinfunction "NFB_3") (pintype "input"))
    )
    (net (code "28") (name "Net-(U7-SW)") (class "Default")
      (node (ref "C15") (pin "1") (pinfunction "1_1") (pintype "passive"))
      (node (ref "L1") (pin "2") (pinfunction "2_2") (pintype "passive"))
      (node (ref "U7") (pin "1") (pinfunction "SW_1") (pintype "power_in"))
    )
    (net (code "29") (name "Net-(U8-SET)") (class "Default")
      (node (ref "C21") (pin "1") (pinfunction "1_1") (pintype "passive"))
      (node (ref "R32") (pin "1") (pinfunction "1_1") (pintype "passive"))
      (node (ref "U8") (pin "8") (pinfunction "SET_8") (pintype "passive"))
    )
    (net (code "30") (name "Net-(U10-TRIM{slash}NR)") (class "Default")
      (node (ref "C7") (pin "1") (pinfunction "1_1") (pintype "passive"))
      (node (ref "U10") (pin "5") (pinfunction "TRIM/NR_5") (pintype "passive"))
    )
    (net (code "31") (name "unconnected-(U3-PG-Pad5)") (class "Default")
      (node (ref "U3") (pin "5") (pinfunction "PG_5") (pintype "passive+no_connect"))
    )
    (net (code "32") (name "unconnected-(U8-PG-Pad4)") (class "Default")
      (node (ref "U8") (pin "4") (pinfunction "PG_4") (pintype "passive+no_connect"))
    )
    (net (code "33") (name "unconnected-(U8-VIOC-Pad7)") (class "Default")
      (node (ref "U8") (pin "7") (pinfunction "VIOC_7") (pintype "passive+no_connect"))
    )
    (net (code "34") (name "unconnected-(U10-DNC-Pad1)") (class "Default")
      (node (ref "U10") (pin "1") (pinfunction "DNC_1") (pintype "passive+no_connect"))
    )
    (net (code "35") (name "unconnected-(U10-DNC-Pad8)") (class "Default")
      (node (ref "U10") (pin "8") (pinfunction "DNC_8") (pintype "passive"))
    )
    (net (code "36") (name "unconnected-(U10-NC-Pad7)") (class "Default")
      (node (ref "U10") (pin "7") (pinfunction "NC_7") (pintype "passive+no_connect"))
    )
    (net (code "37") (name "unconnected-(U10-TEMP-Pad3)") (class "Default")
      (node (ref "U10") (pin "3") (pinfunction "TEMP_3") (pintype "passive"))
    )
  )
)
